# cbm2ram.net
KiCad netlist of a schematic drawn in EAGLE
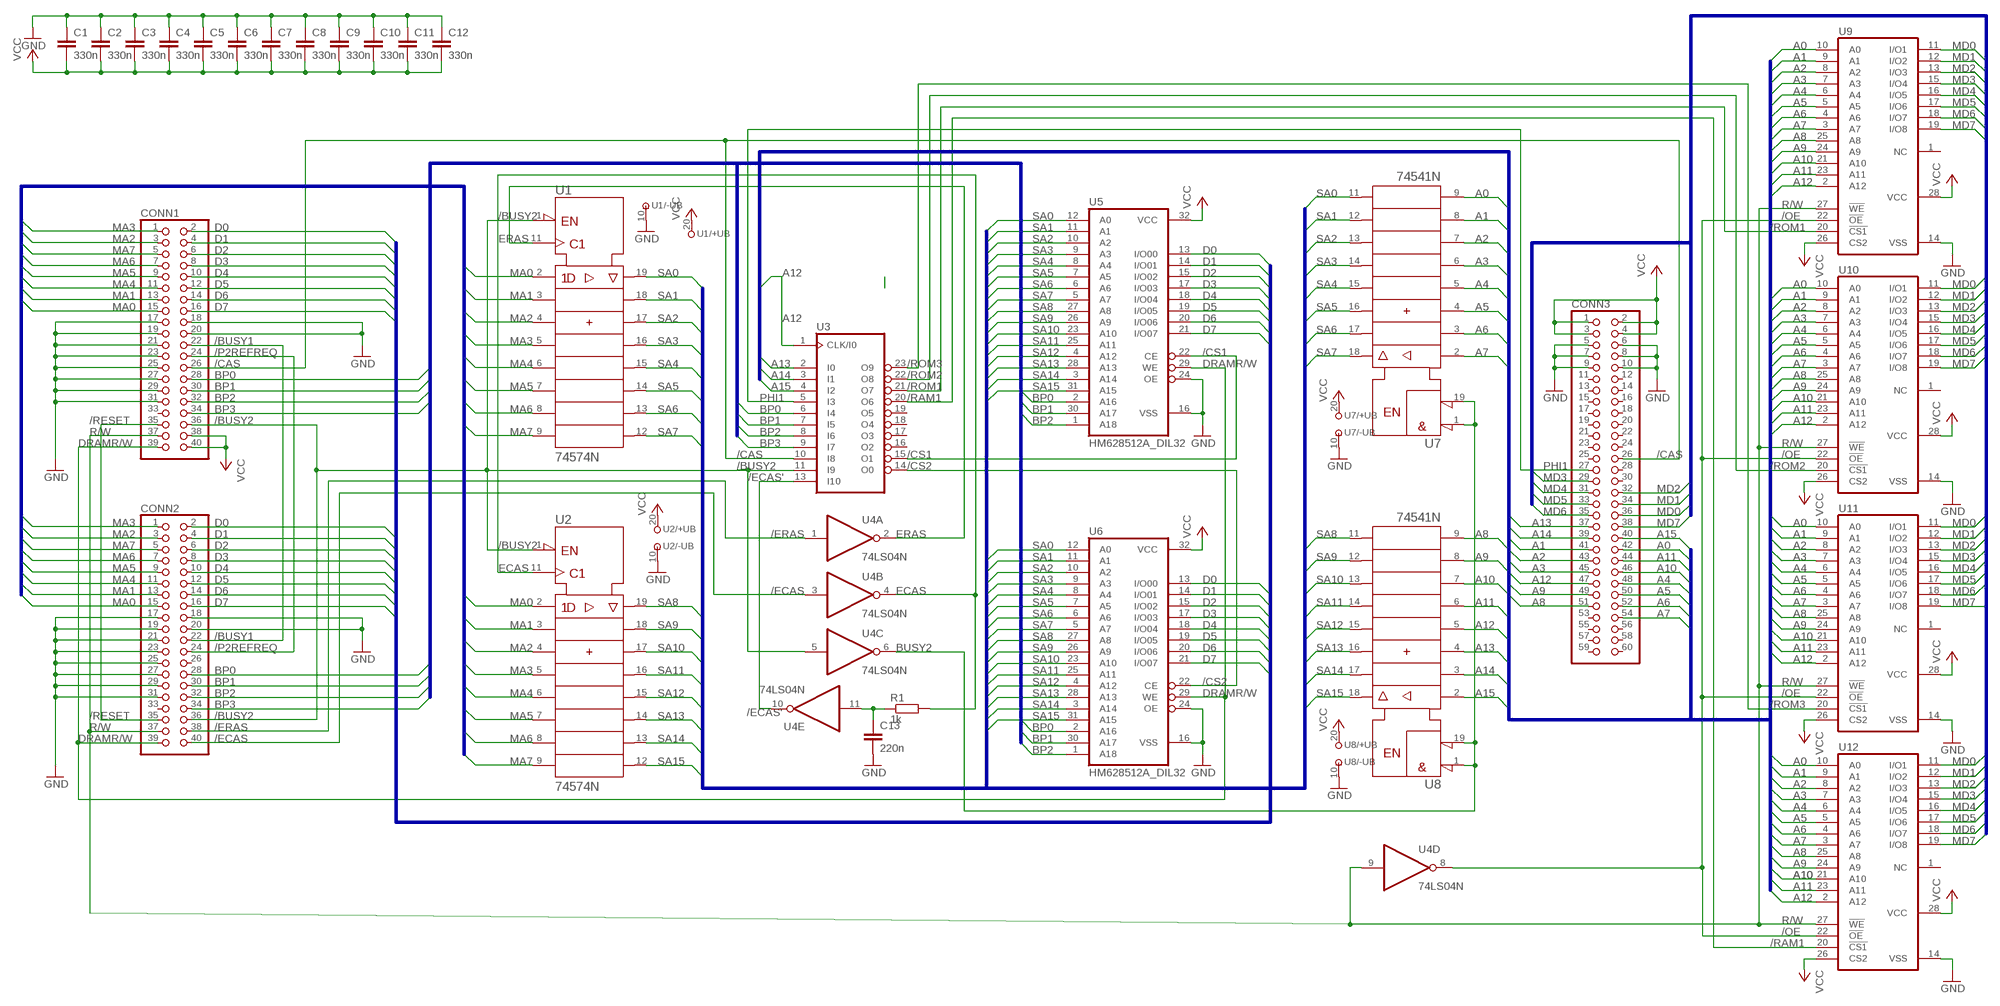
[diagram p0: schematic, sheet 1]

(export (version "E")
  (design (tool "Eeschema 10.0.6"))
  (components
    (comp (ref "C1")
      (value "330n")
      (footprint "eagle-import:C5B3")
      (libsource (lib "eagle-import") (part "C5/3"))
    )
    (comp (ref "C2")
      (value "330n")
      (footprint "eagle-import:C5B3")
      (libsource (lib "eagle-import") (part "C5/3"))
    )
    (comp (ref "C3")
      (value "330n")
      (footprint "eagle-import:C5B3")
      (libsource (lib "eagle-import") (part "C5/3"))
    )
    (comp (ref "C4")
      (value "330n")
      (footprint "eagle-import:C5B3")
      (libsource (lib "eagle-import") (part "C5/3"))
    )
    (comp (ref "C5")
      (value "330n")
      (footprint "eagle-import:C5B3")
      (libsource (lib "eagle-import") (part "C5/3"))
    )
    (comp (ref "C6")
      (value "330n")
      (footprint "eagle-import:C5B3")
      (libsource (lib "eagle-import") (part "C5/3"))
    )
    (comp (ref "C7")
      (value "330n")
      (footprint "eagle-import:C5B3")
      (libsource (lib "eagle-import") (part "C5/3"))
    )
    (comp (ref "C8")
      (value "330n")
      (footprint "eagle-import:C5B3")
      (libsource (lib "eagle-import") (part "C5/3"))
    )
    (comp (ref "C9")
      (value "330n")
      (footprint "eagle-import:C5B3")
      (libsource (lib "eagle-import") (part "C5/3"))
    )
    (comp (ref "C10")
      (value "330n")
      (footprint "eagle-import:C5B3")
      (libsource (lib "eagle-import") (part "C5/3"))
    )
    (comp (ref "C11")
      (value "330n")
      (footprint "eagle-import:C5B3")
      (libsource (lib "eagle-import") (part "C5/3"))
    )
    (comp (ref "C12")
      (value "330n")
      (footprint "eagle-import:C5B3")
      (libsource (lib "eagle-import") (part "C5/3"))
    )
    (comp (ref "C13")
      (value "220n")
      (footprint "eagle-import:C5B3")
      (libsource (lib "eagle-import") (part "C5/3"))
    )
    (comp (ref "CONN1")
      (value "PINHD-2X20")
      (footprint "eagle-import:2X20")
      (libsource (lib "eagle-import") (part "PINHD-2X20"))
    )
    (comp (ref "CONN2")
      (value "PINHD-2X20")
      (footprint "eagle-import:2X20")
      (libsource (lib "eagle-import") (part "PINHD-2X20"))
    )
    (comp (ref "CONN3")
      (value "PINHD-2X30")
      (footprint "eagle-import:2X30")
      (libsource (lib "eagle-import") (part "PINHD-2X30"))
    )
    (comp (ref "R1")
      (value "1k")
      (footprint "eagle-import:0207_10")
      (libsource (lib "eagle-import") (part "R-EU_0207/10"))
    )
    (comp (ref "U1")
      (value "74574N")
      (footprint "eagle-import:DIL20")
      (libsource (lib "eagle-import") (part "74574N"))
    )
    (comp (ref "U2")
      (value "74574N")
      (footprint "eagle-import:DIL20")
      (libsource (lib "eagle-import") (part "74574N"))
    )
    (comp (ref "U3")
      (value "22V10")
      (footprint "eagle-import:DIL24-3")
      (fields (field (name "MPN") "GAL22V10D-7LPN"))
      (libsource (lib "eagle-import") (part "22V10"))
    )
    (comp (ref "U4")
      (value "74LS04N")
      (footprint "eagle-import:DIL14")
      (libsource (lib "eagle-import") (part "7404NLS"))
    )
    (comp (ref "U5")
      (value "HM628512A_DIL32")
      (footprint "eagle-import:DIL32")
      (libsource (lib "eagle-import") (part "HM628512A_DIL32"))
    )
    (comp (ref "U6")
      (value "HM628512A_DIL32")
      (footprint "eagle-import:DIL32")
      (libsource (lib "eagle-import") (part "HM628512A_DIL32"))
    )
    (comp (ref "U7")
      (value "74541N")
      (footprint "eagle-import:DIL20")
      (libsource (lib "eagle-import") (part "74541N"))
    )
    (comp (ref "U8")
      (value "74541N")
      (footprint "eagle-import:DIL20")
      (libsource (lib "eagle-import") (part "74541N"))
    )
    (comp (ref "U9")
      (value "6264A")
      (footprint "eagle-import:DIL28-6")
      (libsource (lib "eagle-import") (part "6264A"))
    )
    (comp (ref "U10")
      (value "6264A")
      (footprint "eagle-import:DIL28-6")
      (libsource (lib "eagle-import") (part "6264A"))
    )
    (comp (ref "U11")
      (value "6264A")
      (footprint "eagle-import:DIL28-6")
      (libsource (lib "eagle-import") (part "6264A"))
    )
    (comp (ref "U12")
      (value "6264A")
      (footprint "eagle-import:DIL28-6")
      (libsource (lib "eagle-import") (part "6264A"))
    )
  )
  (nets
    (net (code "1") (name "/A0") (class "Default")
      (node (ref "CONN3") (pin "42") (pinfunction "42_42") (pintype "passive"))
      (node (ref "U10") (pin "10") (pinfunction "A0_10") (pintype "input"))
      (node (ref "U11") (pin "10") (pinfunction "A0_10") (pintype "input"))
      (node (ref "U12") (pin "10") (pinfunction "A0_10") (pintype "input"))
      (node (ref "U7") (pin "9") (pinfunction "A8_9") (pintype "input"))
      (node (ref "U9") (pin "10") (pinfunction "A0_10") (pintype "input"))
    )
    (net (code "2") (name "/A1") (class "Default")
      (node (ref "CONN3") (pin "41") (pinfunction "41_41") (pintype "passive"))
      (node (ref "U10") (pin "9") (pinfunction "A1_9") (pintype "input"))
      (node (ref "U11") (pin "9") (pinfunction "A1_9") (pintype "input"))
      (node (ref "U12") (pin "9") (pinfunction "A1_9") (pintype "input"))
      (node (ref "U7") (pin "8") (pinfunction "A7_8") (pintype "input"))
      (node (ref "U9") (pin "9") (pinfunction "A1_9") (pintype "input"))
    )
    (net (code "3") (name "/A2") (class "Default")
      (node (ref "CONN3") (pin "43") (pinfunction "43_43") (pintype "passive"))
      (node (ref "U10") (pin "8") (pinfunction "A2_8") (pintype "input"))
      (node (ref "U11") (pin "8") (pinfunction "A2_8") (pintype "input"))
      (node (ref "U12") (pin "8") (pinfunction "A2_8") (pintype "input"))
      (node (ref "U7") (pin "7") (pinfunction "A6_7") (pintype "input"))
      (node (ref "U9") (pin "8") (pinfunction "A2_8") (pintype "input"))
    )
    (net (code "4") (name "/A3") (class "Default")
      (node (ref "CONN3") (pin "45") (pinfunction "45_45") (pintype "passive"))
      (node (ref "U10") (pin "7") (pinfunction "A3_7") (pintype "input"))
      (node (ref "U11") (pin "7") (pinfunction "A3_7") (pintype "input"))
      (node (ref "U12") (pin "7") (pinfunction "A3_7") (pintype "input"))
      (node (ref "U7") (pin "6") (pinfunction "A5_6") (pintype "input"))
      (node (ref "U9") (pin "7") (pinfunction "A3_7") (pintype "input"))
    )
    (net (code "5") (name "/A4") (class "Default")
      (node (ref "CONN3") (pin "48") (pinfunction "48_48") (pintype "passive"))
      (node (ref "U10") (pin "6") (pinfunction "A4_6") (pintype "input"))
      (node (ref "U11") (pin "6") (pinfunction "A4_6") (pintype "input"))
      (node (ref "U12") (pin "6") (pinfunction "A4_6") (pintype "input"))
      (node (ref "U7") (pin "5") (pinfunction "A4_5") (pintype "input"))
      (node (ref "U9") (pin "6") (pinfunction "A4_6") (pintype "input"))
    )
    (net (code "6") (name "/A5") (class "Default")
      (node (ref "CONN3") (pin "50") (pinfunction "50_50") (pintype "passive"))
      (node (ref "U10") (pin "5") (pinfunction "A5_5") (pintype "input"))
      (node (ref "U11") (pin "5") (pinfunction "A5_5") (pintype "input"))
      (node (ref "U12") (pin "5") (pinfunction "A5_5") (pintype "input"))
      (node (ref "U7") (pin "4") (pinfunction "A3_4") (pintype "input"))
      (node (ref "U9") (pin "5") (pinfunction "A5_5") (pintype "input"))
    )
    (net (code "7") (name "/A6") (class "Default")
      (node (ref "CONN3") (pin "52") (pinfunction "52_52") (pintype "passive"))
      (node (ref "U10") (pin "4") (pinfunction "A6_4") (pintype "input"))
      (node (ref "U11") (pin "4") (pinfunction "A6_4") (pintype "input"))
      (node (ref "U12") (pin "4") (pinfunction "A6_4") (pintype "input"))
      (node (ref "U7") (pin "3") (pinfunction "A2_3") (pintype "input"))
      (node (ref "U9") (pin "4") (pinfunction "A6_4") (pintype "input"))
    )
    (net (code "8") (name "/A7") (class "Default")
      (node (ref "CONN3") (pin "54") (pinfunction "54_54") (pintype "passive"))
      (node (ref "U10") (pin "3") (pinfunction "A7_3") (pintype "input"))
      (node (ref "U11") (pin "3") (pinfunction "A7_3") (pintype "input"))
      (node (ref "U12") (pin "3") (pinfunction "A7_3") (pintype "input"))
      (node (ref "U7") (pin "2") (pinfunction "A1_2") (pintype "input"))
      (node (ref "U9") (pin "3") (pinfunction "A7_3") (pintype "input"))
    )
    (net (code "9") (name "/A8") (class "Default")
      (node (ref "CONN3") (pin "51") (pinfunction "51_51") (pintype "passive"))
      (node (ref "U10") (pin "25") (pinfunction "A8_25") (pintype "input"))
      (node (ref "U11") (pin "25") (pinfunction "A8_25") (pintype "input"))
      (node (ref "U12") (pin "25") (pinfunction "A8_25") (pintype "input"))
      (node (ref "U8") (pin "9") (pinfunction "A8_9") (pintype "input"))
      (node (ref "U9") (pin "25") (pinfunction "A8_25") (pintype "input"))
    )
    (net (code "10") (name "/A9") (class "Default")
      (node (ref "CONN3") (pin "49") (pinfunction "49_49") (pintype "passive"))
      (node (ref "U10") (pin "24") (pinfunction "A9_24") (pintype "input"))
      (node (ref "U11") (pin "24") (pinfunction "A9_24") (pintype "input"))
      (node (ref "U12") (pin "24") (pinfunction "A9_24") (pintype "input"))
      (node (ref "U8") (pin "8") (pinfunction "A7_8") (pintype "input"))
      (node (ref "U9") (pin "24") (pinfunction "A9_24") (pintype "input"))
    )
    (net (code "11") (name "/A10") (class "Default")
      (node (ref "CONN3") (pin "46") (pinfunction "46_46") (pintype "passive"))
      (node (ref "U10") (pin "21") (pinfunction "A10_21") (pintype "input"))
      (node (ref "U11") (pin "21") (pinfunction "A10_21") (pintype "input"))
      (node (ref "U12") (pin "21") (pinfunction "A10_21") (pintype "input"))
      (node (ref "U8") (pin "7") (pinfunction "A6_7") (pintype "input"))
      (node (ref "U9") (pin "21") (pinfunction "A10_21") (pintype "input"))
    )
    (net (code "12") (name "/A11") (class "Default")
      (node (ref "CONN3") (pin "44") (pinfunction "44_44") (pintype "passive"))
      (node (ref "U10") (pin "23") (pinfunction "A11_23") (pintype "input"))
      (node (ref "U11") (pin "23") (pinfunction "A11_23") (pintype "input"))
      (node (ref "U12") (pin "23") (pinfunction "A11_23") (pintype "input"))
      (node (ref "U8") (pin "6") (pinfunction "A5_6") (pintype "input"))
      (node (ref "U9") (pin "23") (pinfunction "A11_23") (pintype "input"))
    )
    (net (code "13") (name "/A12") (class "Default")
      (node (ref "CONN3") (pin "47") (pinfunction "47_47") (pintype "passive"))
      (node (ref "U10") (pin "2") (pinfunction "A12_2") (pintype "input"))
      (node (ref "U11") (pin "2") (pinfunction "A12_2") (pintype "input"))
      (node (ref "U12") (pin "2") (pinfunction "A12_2") (pintype "input"))
      (node (ref "U3") (pin "1") (pinfunction "CLK/I0_1") (pintype "input"))
      (node (ref "U8") (pin "5") (pinfunction "A4_5") (pintype "input"))
      (node (ref "U9") (pin "2") (pinfunction "A12_2") (pintype "input"))
    )
    (net (code "14") (name "/A13") (class "Default")
      (node (ref "CONN3") (pin "37") (pinfunction "37_37") (pintype "passive"))
      (node (ref "U3") (pin "2") (pinfunction "I0_2") (pintype "input"))
      (node (ref "U8") (pin "4") (pinfunction "A3_4") (pintype "input"))
    )
    (net (code "15") (name "/A14") (class "Default")
      (node (ref "CONN3") (pin "39") (pinfunction "39_39") (pintype "passive"))
      (node (ref "U3") (pin "3") (pinfunction "I1_3") (pintype "input"))
      (node (ref "U8") (pin "3") (pinfunction "A2_3") (pintype "input"))
    )
    (net (code "16") (name "/A15") (class "Default")
      (node (ref "CONN3") (pin "40") (pinfunction "40_40") (pintype "passive"))
      (node (ref "U3") (pin "4") (pinfunction "I2_4") (pintype "input"))
      (node (ref "U8") (pin "2") (pinfunction "A1_2") (pintype "input"))
    )
    (net (code "17") (name "/BP0") (class "Default")
      (node (ref "CONN1") (pin "28") (pinfunction "28_28") (pintype "passive"))
      (node (ref "CONN2") (pin "28") (pinfunction "28_28") (pintype "passive"))
      (node (ref "U3") (pin "6") (pinfunction "I4_6") (pintype "input"))
      (node (ref "U5") (pin "2") (pinfunction "A16_2") (pintype "input"))
      (node (ref "U6") (pin "2") (pinfunction "A16_2") (pintype "input"))
    )
    (net (code "18") (name "/BP1") (class "Default")
      (node (ref "CONN1") (pin "30") (pinfunction "30_30") (pintype "passive"))
      (node (ref "CONN2") (pin "30") (pinfunction "30_30") (pintype "passive"))
      (node (ref "U3") (pin "7") (pinfunction "I5_7") (pintype "input"))
      (node (ref "U5") (pin "30") (pinfunction "A17_30") (pintype "input"))
      (node (ref "U6") (pin "30") (pinfunction "A17_30") (pintype "input"))
    )
    (net (code "19") (name "/BP2") (class "Default")
      (node (ref "CONN1") (pin "32") (pinfunction "32_32") (pintype "passive"))
      (node (ref "CONN2") (pin "32") (pinfunction "32_32") (pintype "passive"))
      (node (ref "U3") (pin "8") (pinfunction "I6_8") (pintype "input"))
      (node (ref "U5") (pin "1") (pinfunction "A18_1") (pintype "input"))
      (node (ref "U6") (pin "1") (pinfunction "A18_1") (pintype "input"))
    )
    (net (code "20") (name "/BP3") (class "Default")
      (node (ref "CONN1") (pin "34") (pinfunction "34_34") (pintype "passive"))
      (node (ref "CONN2") (pin "34") (pinfunction "34_34") (pintype "passive"))
      (node (ref "U3") (pin "9") (pinfunction "I7_9") (pintype "input"))
    )
    (net (code "21") (name "/BUSY2") (class "Default")
      (node (ref "U4") (pin "6") (pinfunction "O_6") (pintype "output"))
      (node (ref "U7") (pin "1") (pinfunction "~{G1}_1") (pintype "input"))
      (node (ref "U7") (pin "19") (pinfunction "~{G2}_19") (pintype "input"))
      (node (ref "U8") (pin "1") (pinfunction "~{G1}_1") (pintype "input"))
      (node (ref "U8") (pin "19") (pinfunction "~{G2}_19") (pintype "input"))
    )
    (net (code "22") (name "/D0") (class "Default")
      (node (ref "CONN1") (pin "2") (pinfunction "2_2") (pintype "passive"))
      (node (ref "CONN2") (pin "2") (pinfunction "2_2") (pintype "passive"))
      (node (ref "U5") (pin "13") (pinfunction "I/O00_13") (pintype "bidirectional"))
      (node (ref "U6") (pin "13") (pinfunction "I/O00_13") (pintype "bidirectional"))
    )
    (net (code "23") (name "/D1") (class "Default")
      (node (ref "CONN1") (pin "4") (pinfunction "4_4") (pintype "passive"))
      (node (ref "CONN2") (pin "4") (pinfunction "4_4") (pintype "passive"))
      (node (ref "U5") (pin "14") (pinfunction "I/O01_14") (pintype "bidirectional"))
      (node (ref "U6") (pin "14") (pinfunction "I/O01_14") (pintype "bidirectional"))
    )
    (net (code "24") (name "/D2") (class "Default")
      (node (ref "CONN1") (pin "6") (pinfunction "6_6") (pintype "passive"))
      (node (ref "CONN2") (pin "6") (pinfunction "6_6") (pintype "passive"))
      (node (ref "U5") (pin "15") (pinfunction "I/O02_15") (pintype "bidirectional"))
      (node (ref "U6") (pin "15") (pinfunction "I/O02_15") (pintype "bidirectional"))
    )
    (net (code "25") (name "/D3") (class "Default")
      (node (ref "CONN1") (pin "8") (pinfunction "8_8") (pintype "passive"))
      (node (ref "CONN2") (pin "8") (pinfunction "8_8") (pintype "passive"))
      (node (ref "U5") (pin "17") (pinfunction "I/O03_17") (pintype "bidirectional"))
      (node (ref "U6") (pin "17") (pinfunction "I/O03_17") (pintype "bidirectional"))
    )
    (net (code "26") (name "/D4") (class "Default")
      (node (ref "CONN1") (pin "10") (pinfunction "10_10") (pintype "passive"))
      (node (ref "CONN2") (pin "10") (pinfunction "10_10") (pintype "passive"))
      (node (ref "U5") (pin "18") (pinfunction "I/O04_18") (pintype "bidirectional"))
      (node (ref "U6") (pin "18") (pinfunction "I/O04_18") (pintype "bidirectional"))
    )
    (net (code "27") (name "/D5") (class "Default")
      (node (ref "CONN1") (pin "12") (pinfunction "12_12") (pintype "passive"))
      (node (ref "CONN2") (pin "12") (pinfunction "12_12") (pintype "passive"))
      (node (ref "U5") (pin "19") (pinfunction "I/O05_19") (pintype "bidirectional"))
      (node (ref "U6") (pin "19") (pinfunction "I/O05_19") (pintype "bidirectional"))
    )
    (net (code "28") (name "/D6") (class "Default")
      (node (ref "CONN1") (pin "14") (pinfunction "14_14") (pintype "passive"))
      (node (ref "CONN2") (pin "14") (pinfunction "14_14") (pintype "passive"))
      (node (ref "U5") (pin "20") (pinfunction "I/O06_20") (pintype "bidirectional"))
      (node (ref "U6") (pin "20") (pinfunction "I/O06_20") (pintype "bidirectional"))
    )
    (net (code "29") (name "/D7") (class "Default")
      (node (ref "CONN1") (pin "16") (pinfunction "16_16") (pintype "passive"))
      (node (ref "CONN2") (pin "16") (pinfunction "16_16") (pintype "passive"))
      (node (ref "U5") (pin "21") (pinfunction "I/O07_21") (pintype "bidirectional"))
      (node (ref "U6") (pin "21") (pinfunction "I/O07_21") (pintype "bidirectional"))
    )
    (net (code "30") (name "/DRAMR{slash}W") (class "Default")
      (node (ref "CONN1") (pin "39") (pinfunction "39_39") (pintype "passive"))
      (node (ref "CONN2") (pin "39") (pinfunction "39_39") (pintype "passive"))
      (node (ref "U5") (pin "29") (pinfunction "WE_29") (pintype "input"))
      (node (ref "U6") (pin "29") (pinfunction "WE_29") (pintype "input"))
    )
    (net (code "31") (name "/ECAS") (class "Default")
      (node (ref "R1") (pin "2") (pinfunction "2_2") (pintype "passive"))
      (node (ref "U2") (pin "11") (pinfunction "CLK_11") (pintype "input"))
      (node (ref "U4") (pin "4") (pinfunction "O_4") (pintype "output"))
    )
    (net (code "32") (name "/ERAS") (class "Default")
      (node (ref "U1") (pin "11") (pinfunction "CLK_11") (pintype "input"))
      (node (ref "U4") (pin "2") (pinfunction "O_2") (pintype "output"))
    )
    (net (code "33") (name "/MA0") (class "Default")
      (node (ref "CONN1") (pin "15") (pinfunction "15_15") (pintype "passive"))
      (node (ref "CONN2") (pin "15") (pinfunction "15_15") (pintype "passive"))
      (node (ref "U1") (pin "2") (pinfunction "1D_2") (pintype "input"))
      (node (ref "U2") (pin "2") (pinfunction "1D_2") (pintype "input"))
    )
    (net (code "34") (name "/MA1") (class "Default")
      (node (ref "CONN1") (pin "13") (pinfunction "13_13") (pintype "passive"))
      (node (ref "CONN2") (pin "13") (pinfunction "13_13") (pintype "passive"))
      (node (ref "U1") (pin "3") (pinfunction "2D_3") (pintype "input"))
      (node (ref "U2") (pin "3") (pinfunction "2D_3") (pintype "input"))
    )
    (net (code "35") (name "/MA2") (class "Default")
      (node (ref "CONN1") (pin "3") (pinfunction "3_3") (pintype "passive"))
      (node (ref "CONN2") (pin "3") (pinfunction "3_3") (pintype "passive"))
      (node (ref "U1") (pin "4") (pinfunction "3D_4") (pintype "input"))
      (node (ref "U2") (pin "4") (pinfunction "3D_4") (pintype "input"))
    )
    (net (code "36") (name "/MA3") (class "Default")
      (node (ref "CONN1") (pin "1") (pinfunction "1_1") (pintype "passive"))
      (node (ref "CONN2") (pin "1") (pinfunction "1_1") (pintype "passive"))
      (node (ref "U1") (pin "5") (pinfunction "4D_5") (pintype "input"))
      (node (ref "U2") (pin "5") (pinfunction "4D_5") (pintype "input"))
    )
    (net (code "37") (name "/MA4") (class "Default")
      (node (ref "CONN1") (pin "11") (pinfunction "11_11") (pintype "passive"))
      (node (ref "CONN2") (pin "11") (pinfunction "11_11") (pintype "passive"))
      (node (ref "U1") (pin "6") (pinfunction "5D_6") (pintype "input"))
      (node (ref "U2") (pin "6") (pinfunction "5D_6") (pintype "input"))
    )
    (net (code "38") (name "/MA5") (class "Default")
      (node (ref "CONN1") (pin "9") (pinfunction "9_9") (pintype "passive"))
      (node (ref "CONN2") (pin "9") (pinfunction "9_9") (pintype "passive"))
      (node (ref "U1") (pin "7") (pinfunction "6D_7") (pintype "input"))
      (node (ref "U2") (pin "7") (pinfunction "6D_7") (pintype "input"))
    )
    (net (code "39") (name "/MA6") (class "Default")
      (node (ref "CONN1") (pin "7") (pinfunction "7_7") (pintype "passive"))
      (node (ref "CONN2") (pin "7") (pinfunction "7_7") (pintype "passive"))
      (node (ref "U1") (pin "8") (pinfunction "7D_8") (pintype "input"))
      (node (ref "U2") (pin "8") (pinfunction "7D_8") (pintype "input"))
    )
    (net (code "40") (name "/MA7") (class "Default")
      (node (ref "CONN1") (pin "5") (pinfunction "5_5") (pintype "passive"))
      (node (ref "CONN2") (pin "5") (pinfunction "5_5") (pintype "passive"))
      (node (ref "U1") (pin "9") (pinfunction "8D_9") (pintype "input"))
      (node (ref "U2") (pin "9") (pinfunction "8D_9") (pintype "input"))
    )
    (net (code "41") (name "/MD0") (class "Default")
      (node (ref "CONN3") (pin "36") (pinfunction "36_36") (pintype "passive"))
      (node (ref "U10") (pin "11") (pinfunction "I/O1_11") (pintype "bidirectional"))
      (node (ref "U11") (pin "11") (pinfunction "I/O1_11") (pintype "bidirectional"))
      (node (ref "U12") (pin "11") (pinfunction "I/O1_11") (pintype "bidirectional"))
      (node (ref "U9") (pin "11") (pinfunction "I/O1_11") (pintype "bidirectional"))
    )
    (net (code "42") (name "/MD1") (class "Default")
      (node (ref "CONN3") (pin "34") (pinfunction "34_34") (pintype "passive"))
      (node (ref "U10") (pin "12") (pinfunction "I/O2_12") (pintype "bidirectional"))
      (node (ref "U11") (pin "12") (pinfunction "I/O2_12") (pintype "bidirectional"))
      (node (ref "U12") (pin "12") (pinfunction "I/O2_12") (pintype "bidirectional"))
      (node (ref "U9") (pin "12") (pinfunction "I/O2_12") (pintype "bidirectional"))
    )
    (net (code "43") (name "/MD2") (class "Default")
      (node (ref "CONN3") (pin "32") (pinfunction "32_32") (pintype "passive"))
      (node (ref "U10") (pin "13") (pinfunction "I/O3_13") (pintype "bidirectional"))
      (node (ref "U11") (pin "13") (pinfunction "I/O3_13") (pintype "bidirectional"))
      (node (ref "U12") (pin "13") (pinfunction "I/O3_13") (pintype "bidirectional"))
      (node (ref "U9") (pin "13") (pinfunction "I/O3_13") (pintype "bidirectional"))
    )
    (net (code "44") (name "/MD3") (class "Default")
      (node (ref "CONN3") (pin "29") (pinfunction "29_29") (pintype "passive"))
      (node (ref "U10") (pin "15") (pinfunction "I/O4_15") (pintype "bidirectional"))
      (node (ref "U11") (pin "15") (pinfunction "I/O4_15") (pintype "bidirectional"))
      (node (ref "U12") (pin "15") (pinfunction "I/O4_15") (pintype "bidirectional"))
      (node (ref "U9") (pin "15") (pinfunction "I/O4_15") (pintype "bidirectional"))
    )
    (net (code "45") (name "/MD4") (class "Default")
      (node (ref "CONN3") (pin "31") (pinfunction "31_31") (pintype "passive"))
      (node (ref "U10") (pin "16") (pinfunction "I/O5_16") (pintype "bidirectional"))
      (node (ref "U11") (pin "16") (pinfunction "I/O5_16") (pintype "bidirectional"))
      (node (ref "U12") (pin "16") (pinfunction "I/O5_16") (pintype "bidirectional"))
      (node (ref "U9") (pin "16") (pinfunction "I/O5_16") (pintype "bidirectional"))
    )
    (net (code "46") (name "/MD5") (class "Default")
      (node (ref "CONN3") (pin "33") (pinfunction "33_33") (pintype "passive"))
      (node (ref "U10") (pin "17") (pinfunction "I/O6_17") (pintype "bidirectional"))
      (node (ref "U11") (pin "17") (pinfunction "I/O6_17") (pintype "bidirectional"))
      (node (ref "U12") (pin "17") (pinfunction "I/O6_17") (pintype "bidirectional"))
      (node (ref "U9") (pin "17") (pinfunction "I/O6_17") (pintype "bidirectional"))
    )
    (net (code "47") (name "/MD6") (class "Default")
      (node (ref "CONN3") (pin "35") (pinfunction "35_35") (pintype "passive"))
      (node (ref "U10") (pin "18") (pinfunction "I/O7_18") (pintype "bidirectional"))
      (node (ref "U11") (pin "18") (pinfunction "I/O7_18") (pintype "bidirectional"))
      (node (ref "U12") (pin "18") (pinfunction "I/O7_18") (pintype "bidirectional"))
      (node (ref "U9") (pin "18") (pinfunction "I/O7_18") (pintype "bidirectional"))
    )
    (net (code "48") (name "/MD7") (class "Default")
      (node (ref "CONN3") (pin "38") (pinfunction "38_38") (pintype "passive"))
      (node (ref "U10") (pin "19") (pinfunction "I/O8_19") (pintype "bidirectional"))
      (node (ref "U11") (pin "19") (pinfunction "I/O8_19") (pintype "bidirectional"))
      (node (ref "U12") (pin "19") (pinfunction "I/O8_19") (pintype "bidirectional"))
      (node (ref "U9") (pin "19") (pinfunction "I/O8_19") (pintype "bidirectional"))
    )
    (net (code "49") (name "/PHI1") (class "Default")
      (node (ref "CONN3") (pin "27") (pinfunction "27_27") (pintype "passive"))
      (node (ref "U3") (pin "5") (pinfunction "I3_5") (pintype "input"))
    )
    (net (code "50") (name "/R{slash}W") (class "Default")
      (node (ref "CONN1") (pin "37") (pinfunction "37_37") (pintype "passive"))
      (node (ref "CONN2") (pin "37") (pinfunction "37_37") (pintype "passive"))
      (node (ref "U10") (pin "27") (pinfunction "~{WE}_27") (pintype "input"))
      (node (ref "U11") (pin "27") (pinfunction "~{WE}_27") (pintype "input"))
      (node (ref "U12") (pin "27") (pinfunction "~{WE}_27") (pintype "input"))
      (node (ref "U4") (pin "9") (pinfunction "I_9") (pintype "input"))
      (node (ref "U9") (pin "27") (pinfunction "~{WE}_27") (pintype "input"))
    )
    (net (code "51") (name "/SA0") (class "Default")
      (node (ref "U1") (pin "19") (pinfunction "1Q_19") (pintype "tri_state"))
      (node (ref "U5") (pin "12") (pinfunction "A0_12") (pintype "input"))
      (node (ref "U6") (pin "12") (pinfunction "A0_12") (pintype "input"))
      (node (ref "U7") (pin "11") (pinfunction "Y8_11") (pintype "tri_state"))
    )
    (net (code "52") (name "/SA1") (class "Default")
      (node (ref "U1") (pin "18") (pinfunction "2Q_18") (pintype "tri_state"))
      (node (ref "U5") (pin "11") (pinfunction "A1_11") (pintype "input"))
      (node (ref "U6") (pin "11") (pinfunction "A1_11") (pintype "input"))
      (node (ref "U7") (pin "12") (pinfunction "Y7_12") (pintype "tri_state"))
    )
    (net (code "53") (name "/SA2") (class "Default")
      (node (ref "U1") (pin "17") (pinfunction "3Q_17") (pintype "tri_state"))
      (node (ref "U5") (pin "10") (pinfunction "A2_10") (pintype "input"))
      (node (ref "U6") (pin "10") (pinfunction "A2_10") (pintype "input"))
      (node (ref "U7") (pin "13") (pinfunction "Y6_13") (pintype "tri_state"))
    )
    (net (code "54") (name "/SA3") (class "Default")
      (node (ref "U1") (pin "16") (pinfunction "4Q_16") (pintype "tri_state"))
      (node (ref "U5") (pin "9") (pinfunction "A3_9") (pintype "input"))
      (node (ref "U6") (pin "9") (pinfunction "A3_9") (pintype "input"))
      (node (ref "U7") (pin "14") (pinfunction "Y5_14") (pintype "tri_state"))
    )
    (net (code "55") (name "/SA4") (class "Default")
      (node (ref "U1") (pin "15") (pinfunction "5Q_15") (pintype "tri_state"))
      (node (ref "U5") (pin "8") (pinfunction "A4_8") (pintype "input"))
      (node (ref "U6") (pin "8") (pinfunction "A4_8") (pintype "input"))
      (node (ref "U7") (pin "15") (pinfunction "Y4_15") (pintype "tri_state"))
    )
    (net (code "56") (name "/SA5") (class "Default")
      (node (ref "U1") (pin "14") (pinfunction "6Q_14") (pintype "tri_state"))
      (node (ref "U5") (pin "7") (pinfunction "A5_7") (pintype "input"))
      (node (ref "U6") (pin "7") (pinfunction "A5_7") (pintype "input"))
      (node (ref "U7") (pin "16") (pinfunction "Y3_16") (pintype "tri_state"))
    )
    (net (code "57") (name "/SA6") (class "Default")
      (node (ref "U1") (pin "13") (pinfunction "7Q_13") (pintype "tri_state"))
      (node (ref "U5") (pin "6") (pinfunction "A6_6") (pintype "input"))
      (node (ref "U6") (pin "6") (pinfunction "A6_6") (pintype "input"))
      (node (ref "U7") (pin "17") (pinfunction "Y2_17") (pintype "tri_state"))
    )
    (net (code "58") (name "/SA7") (class "Default")
      (node (ref "U1") (pin "12") (pinfunction "8Q_12") (pintype "tri_state"))
      (node (ref "U5") (pin "5") (pinfunction "A7_5") (pintype "input"))
      (node (ref "U6") (pin "5") (pinfunction "A7_5") (pintype "input"))
      (node (ref "U7") (pin "18") (pinfunction "Y1_18") (pintype "tri_state"))
    )
    (net (code "59") (name "/SA8") (class "Default")
      (node (ref "U2") (pin "19") (pinfunction "1Q_19") (pintype "tri_state"))
      (node (ref "U5") (pin "27") (pinfunction "A8_27") (pintype "input"))
      (node (ref "U6") (pin "27") (pinfunction "A8_27") (pintype "input"))
      (node (ref "U8") (pin "11") (pinfunction "Y8_11") (pintype "tri_state"))
    )
    (net (code "60") (name "/SA9") (class "Default")
      (node (ref "U2") (pin "18") (pinfunction "2Q_18") (pintype "tri_state"))
      (node (ref "U5") (pin "26") (pinfunction "A9_26") (pintype "input"))
      (node (ref "U6") (pin "26") (pinfunction "A9_26") (pintype "input"))
      (node (ref "U8") (pin "12") (pinfunction "Y7_12") (pintype "tri_state"))
    )
    (net (code "61") (name "/SA10") (class "Default")
      (node (ref "U2") (pin "17") (pinfunction "3Q_17") (pintype "tri_state"))
      (node (ref "U5") (pin "23") (pinfunction "A10_23") (pintype "input"))
      (node (ref "U6") (pin "23") (pinfunction "A10_23") (pintype "input"))
      (node (ref "U8") (pin "13") (pinfunction "Y6_13") (pintype "tri_state"))
    )
    (net (code "62") (name "/SA11") (class "Default")
      (node (ref "U2") (pin "16") (pinfunction "4Q_16") (pintype "tri_state"))
      (node (ref "U5") (pin "25") (pinfunction "A11_25") (pintype "input"))
      (node (ref "U6") (pin "25") (pinfunction "A11_25") (pintype "input"))
      (node (ref "U8") (pin "14") (pinfunction "Y5_14") (pintype "tri_state"))
    )
    (net (code "63") (name "/SA12") (class "Default")
      (node (ref "U2") (pin "15") (pinfunction "5Q_15") (pintype "tri_state"))
      (node (ref "U5") (pin "4") (pinfunction "A12_4") (pintype "input"))
      (node (ref "U6") (pin "4") (pinfunction "A12_4") (pintype "input"))
      (node (ref "U8") (pin "15") (pinfunction "Y4_15") (pintype "tri_state"))
    )
    (net (code "64") (name "/SA13") (class "Default")
      (node (ref "U2") (pin "14") (pinfunction "6Q_14") (pintype "tri_state"))
      (node (ref "U5") (pin "28") (pinfunction "A13_28") (pintype "input"))
      (node (ref "U6") (pin "28") (pinfunction "A13_28") (pintype "input"))
      (node (ref "U8") (pin "16") (pinfunction "Y3_16") (pintype "tri_state"))
    )
    (net (code "65") (name "/SA14") (class "Default")
      (node (ref "U2") (pin "13") (pinfunction "7Q_13") (pintype "tri_state"))
      (node (ref "U5") (pin "3") (pinfunction "A14_3") (pintype "input"))
      (node (ref "U6") (pin "3") (pinfunction "A14_3") (pintype "input"))
      (node (ref "U8") (pin "17") (pinfunction "Y2_17") (pintype "tri_state"))
    )
    (net (code "66") (name "/SA15") (class "Default")
      (node (ref "U2") (pin "12") (pinfunction "8Q_12") (pintype "tri_state"))
      (node (ref "U5") (pin "31") (pinfunction "A15_31") (pintype "input"))
      (node (ref "U6") (pin "31") (pinfunction "A15_31") (pintype "input"))
      (node (ref "U8") (pin "18") (pinfunction "Y1_18") (pintype "tri_state"))
    )
    (net (code "67") (name "/{slash}BUSY1") (class "Default")
      (node (ref "CONN1") (pin "22") (pinfunction "22_22") (pintype "passive"))
      (node (ref "CONN2") (pin "22") (pinfunction "22_22") (pintype "passive"))
    )
    (net (code "68") (name "/{slash}BUSY2") (class "Default")
      (node (ref "CONN1") (pin "36") (pinfunction "36_36") (pintype "passive"))
      (node (ref "CONN2") (pin "36") (pinfunction "36_36") (pintype "passive"))
      (node (ref "U1") (pin "1") (pinfunction "~{OC}_1") (pintype "input"))
      (node (ref "U2") (pin "1") (pinfunction "~{OC}_1") (pintype "input"))
      (node (ref "U3") (pin "11") (pinfunction "I9_11") (pintype "input"))
      (node (ref "U4") (pin "5") (pinfunction "I_5") (pintype "input"))
    )
    (net (code "69") (name "/{slash}CAS") (class "Default")
      (node (ref "CONN1") (pin "26") (pinfunction "26_26") (pintype "passive"))
      (node (ref "CONN3") (pin "26") (pinfunction "26_26") (pintype "passive"))
      (node (ref "U3") (pin "10") (pinfunction "I8_10") (pintype "input"))
    )
    (net (code "70") (name "/{slash}CS1") (class "Default")
      (node (ref "U3") (pin "15") (pinfunction "O1_15") (pintype "bidirectional"))
      (node (ref "U5") (pin "22") (pinfunction "CE_22") (pintype "input"))
    )
    (net (code "71") (name "/{slash}CS2") (class "Default")
      (node (ref "U3") (pin "14") (pinfunction "O0_14") (pintype "bidirectional"))
      (node (ref "U6") (pin "22") (pinfunction "CE_22") (pintype "input"))
    )
    (net (code "72") (name "/{slash}ECAS") (class "Default")
      (node (ref "CONN2") (pin "40") (pinfunction "40_40") (pintype "passive"))
      (node (ref "U4") (pin "3") (pinfunction "I_3") (pintype "input"))
    )
    (net (code "73") (name "/{slash}ECAS'") (class "Default")
      (node (ref "U3") (pin "13") (pinfunction "I10_13") (pintype "input"))
      (node (ref "U4") (pin "10") (pinfunction "O_10") (pintype "output"))
    )
    (net (code "74") (name "/{slash}ERAS") (class "Default")
      (node (ref "CONN2") (pin "38") (pinfunction "38_38") (pintype "passive"))
      (node (ref "U4") (pin "1") (pinfunction "I_1") (pintype "input"))
    )
    (net (code "75") (name "/{slash}OE") (class "Default")
      (node (ref "U10") (pin "22") (pinfunction "~{OE}_22") (pintype "input"))
      (node (ref "U11") (pin "22") (pinfunction "~{OE}_22") (pintype "input"))
      (node (ref "U12") (pin "22") (pinfunction "~{OE}_22") (pintype "input"))
      (node (ref "U4") (pin "8") (pinfunction "O_8") (pintype "output"))
      (node (ref "U9") (pin "22") (pinfunction "~{OE}_22") (pintype "input"))
    )
    (net (code "76") (name "/{slash}P2REFREQ") (class "Default")
      (node (ref "CONN1") (pin "24") (pinfunction "24_24") (pintype "passive"))
      (node (ref "CONN2") (pin "24") (pinfunction "24_24") (pintype "passive"))
    )
    (net (code "77") (name "/{slash}RAM1") (class "Default")
      (node (ref "U12") (pin "20") (pinfunction "~{CS1}_20") (pintype "input"))
      (node (ref "U3") (pin "20") (pinfunction "O6_20") (pintype "bidirectional"))
    )
    (net (code "78") (name "/{slash}RESET") (class "Default")
      (node (ref "CONN1") (pin "35") (pinfunction "35_35") (pintype "passive"))
      (node (ref "CONN2") (pin "35") (pinfunction "35_35") (pintype "passive"))
    )
    (net (code "79") (name "/{slash}ROM1") (class "Default")
      (node (ref "U3") (pin "21") (pinfunction "O7_21") (pintype "bidirectional"))
      (node (ref "U9") (pin "20") (pinfunction "~{CS1}_20") (pintype "input"))
    )
    (net (code "80") (name "/{slash}ROM2") (class "Default")
      (node (ref "U10") (pin "20") (pinfunction "~{CS1}_20") (pintype "input"))
      (node (ref "U3") (pin "22") (pinfunction "O8_22") (pintype "bidirectional"))
    )
    (net (code "81") (name "/{slash}ROM3") (class "Default")
      (node (ref "U11") (pin "20") (pinfunction "~{CS1}_20") (pintype "input"))
      (node (ref "U3") (pin "23") (pinfunction "O9_23") (pintype "bidirectional"))
    )
    (net (code "82") (name "GND") (class "Default")
      (node (ref "C1") (pin "1") (pinfunction "1_1") (pintype "passive"))
      (node (ref "C10") (pin "1") (pinfunction "1_1") (pintype "passive"))
      (node (ref "C11") (pin "1") (pinfunction "1_1") (pintype "passive"))
      (node (ref "C12") (pin "1") (pinfunction "1_1") (pintype "passive"))
      (node (ref "C13") (pin "2") (pinfunction "2_2") (pintype "passive"))
      (node (ref "C2") (pin "1") (pinfunction "1_1") (pintype "passive"))
      (node (ref "C3") (pin "1") (pinfunction "1_1") (pintype "passive"))
      (node (ref "C4") (pin "1") (pinfunction "1_1") (pintype "passive"))
      (node (ref "C5") (pin "1") (pinfunction "1_1") (pintype "passive"))
      (node (ref "C6") (pin "1") (pinfunction "1_1") (pintype "passive"))
      (node (ref "C7") (pin "1") (pinfunction "1_1") (pintype "passive"))
      (node (ref "C8") (pin "1") (pinfunction "1_1") (pintype "passive"))
      (node (ref "C9") (pin "1") (pinfunction "1_1") (pintype "passive"))
      (node (ref "CONN1") (pin "17") (pinfunction "17_17") (pintype "passive"))
      (node (ref "CONN1") (pin "18") (pinfunction "18_18") (pintype "passive"))
      (node (ref "CONN1") (pin "19") (pinfunction "19_19") (pintype "passive"))
      (node (ref "CONN1") (pin "20") (pinfunction "20_20") (pintype "passive"))
      (node (ref "CONN1") (pin "21") (pinfunction "21_21") (pintype "passive"))
      (node (ref "CONN1") (pin "23") (pinfunction "23_23") (pintype "passive"))
      (node (ref "CONN1") (pin "25") (pinfunction "25_25") (pintype "passive"))
      (node (ref "CONN1") (pin "27") (pinfunction "27_27") (pintype "passive"))
      (node (ref "CONN1") (pin "29") (pinfunction "29_29") (pintype "passive"))
      (node (ref "CONN1") (pin "31") (pinfunction "31_31") (pintype "passive"))
      (node (ref "CONN2") (pin "17") (pinfunction "17_17") (pintype "passive"))
      (node (ref "CONN2") (pin "18") (pinfunction "18_18") (pintype "passive"))
      (node (ref "CONN2") (pin "19") (pinfunction "19_19") (pintype "passive"))
      (node (ref "CONN2") (pin "20") (pinfunction "20_20") (pintype "passive"))
      (node (ref "CONN2") (pin "21") (pinfunction "21_21") (pintype "passive"))
      (node (ref "CONN2") (pin "23") (pinfunction "23_23") (pintype "passive"))
      (node (ref "CONN2") (pin "25") (pinfunction "25_25") (pintype "passive"))
      (node (ref "CONN2") (pin "27") (pinfunction "27_27") (pintype "passive"))
      (node (ref "CONN2") (pin "29") (pinfunction "29_29") (pintype "passive"))
      (node (ref "CONN2") (pin "31") (pinfunction "31_31") (pintype "passive"))
      (node (ref "CONN3") (pin "10") (pinfunction "10_10") (pintype "passive"))
      (node (ref "CONN3") (pin "5") (pinfunction "5_5") (pintype "passive"))
      (node (ref "CONN3") (pin "6") (pinfunction "6_6") (pintype "passive"))
      (node (ref "CONN3") (pin "7") (pinfunction "7_7") (pintype "passive"))
      (node (ref "CONN3") (pin "8") (pinfunction "8_8") (pintype "passive"))
      (node (ref "CONN3") (pin "9") (pinfunction "9_9") (pintype "passive"))
      (node (ref "U1") (pin "10") (pinfunction "-UB_10") (pintype "power_in"))
      (node (ref "U10") (pin "14") (pinfunction "VSS_14") (pintype "power_in"))
      (node (ref "U11") (pin "14") (pinfunction "VSS_14") (pintype "power_in"))
      (node (ref "U12") (pin "14") (pinfunction "VSS_14") (pintype "power_in"))
      (node (ref "U2") (pin "10") (pinfunction "-UB_10") (pintype "power_in"))
      (node (ref "U5") (pin "16") (pinfunction "VSS_16") (pintype "power_in"))
      (node (ref "U5") (pin "24") (pinfunction "OE_24") (pintype "input"))
      (node (ref "U6") (pin "16") (pinfunction "VSS_16") (pintype "power_in"))
      (node (ref "U6") (pin "24") (pinfunction "OE_24") (pintype "input"))
      (node (ref "U7") (pin "10") (pinfunction "-UB_10") (pintype "power_in"))
      (node (ref "U8") (pin "10") (pinfunction "-UB_10") (pintype "power_in"))
      (node (ref "U9") (pin "14") (pinfunction "VSS_14") (pintype "power_in"))
    )
    (net (code "83") (name "Net-(U4E-I)") (class "Default")
      (node (ref "C13") (pin "1") (pinfunction "1_1") (pintype "passive"))
      (node (ref "R1") (pin "1") (pinfunction "1_1") (pintype "passive"))
      (node (ref "U4") (pin "11") (pinfunction "I_11") (pintype "input"))
    )
    (net (code "84") (name "VCC") (class "Default")
      (node (ref "C1") (pin "2") (pinfunction "2_2") (pintype "passive"))
      (node (ref "C10") (pin "2") (pinfunction "2_2") (pintype "passive"))
      (node (ref "C11") (pin "2") (pinfunction "2_2") (pintype "passive"))
      (node (ref "C12") (pin "2") (pinfunction "2_2") (pintype "passive"))
      (node (ref "C2") (pin "2") (pinfunction "2_2") (pintype "passive"))
      (node (ref "C3") (pin "2") (pinfunction "2_2") (pintype "passive"))
      (node (ref "C4") (pin "2") (pinfunction "2_2") (pintype "passive"))
      (node (ref "C5") (pin "2") (pinfunction "2_2") (pintype "passive"))
      (node (ref "C6") (pin "2") (pinfunction "2_2") (pintype "passive"))
      (node (ref "C7") (pin "2") (pinfunction "2_2") (pintype "passive"))
      (node (ref "C8") (pin "2") (pinfunction "2_2") (pintype "passive"))
      (node (ref "C9") (pin "2") (pinfunction "2_2") (pintype "passive"))
      (node (ref "CONN1") (pin "38") (pinfunction "38_38") (pintype "passive"))
      (node (ref "CONN1") (pin "40") (pinfunction "40_40") (pintype "passive"))
      (node (ref "CONN3") (pin "1") (pinfunction "1_1") (pintype "passive"))
      (node (ref "CONN3") (pin "2") (pinfunction "2_2") (pintype "passive"))
      (node (ref "CONN3") (pin "3") (pinfunction "3_3") (pintype "passive"))
      (node (ref "CONN3") (pin "4") (pinfunction "4_4") (pintype "passive"))
      (node (ref "U1") (pin "20") (pinfunction "+UB_20") (pintype "power_in"))
      (node (ref "U10") (pin "26") (pinfunction "CS2_26") (pintype "input"))
      (node (ref "U10") (pin "28") (pinfunction "VCC_28") (pintype "power_in"))
      (node (ref "U11") (pin "26") (pinfunction "CS2_26") (pintype "input"))
      (node (ref "U11") (pin "28") (pinfunction "VCC_28") (pintype "power_in"))
      (node (ref "U12") (pin "26") (pinfunction "CS2_26") (pintype "input"))
      (node (ref "U12") (pin "28") (pinfunction "VCC_28") (pintype "power_in"))
      (node (ref "U2") (pin "20") (pinfunction "+UB_20") (pintype "power_in"))
      (node (ref "U5") (pin "32") (pinfunction "VCC_32") (pintype "power_in"))
      (node (ref "U6") (pin "32") (pinfunction "VCC_32") (pintype "power_in"))
      (node (ref "U7") (pin "20") (pinfunction "+UB_20") (pintype "power_in"))
      (node (ref "U8") (pin "20") (pinfunction "+UB_20") (pintype "power_in"))
      (node (ref "U9") (pin "26") (pinfunction "CS2_26") (pintype "input"))
      (node (ref "U9") (pin "28") (pinfunction "VCC_28") (pintype "power_in"))
    )
    (net (code "85") (name "unconnected-(CONN1-Pad33)") (class "Default")
      (node (ref "CONN1") (pin "33") (pinfunction "33_33") (pintype "passive"))
    )
    (net (code "86") (name "unconnected-(CONN2-Pad26)") (class "Default")
      (node (ref "CONN2") (pin "26") (pinfunction "26_26") (pintype "passive"))
    )
    (net (code "87") (name "unconnected-(CONN2-Pad33)") (class "Default")
      (node (ref "CONN2") (pin "33") (pinfunction "33_33") (pintype "passive"))
    )
    (net (code "88") (name "unconnected-(CONN3-Pad11)") (class "Default")
      (node (ref "CONN3") (pin "11") (pinfunction "11_11") (pintype "passive"))
    )
    (net (code "89") (name "unconnected-(CONN3-Pad12)") (class "Default")
      (node (ref "CONN3") (pin "12") (pinfunction "12_12") (pintype "passive"))
    )
    (net (code "90") (name "unconnected-(CONN3-Pad13)") (class "Default")
      (node (ref "CONN3") (pin "13") (pinfunction "13_13") (pintype "passive"))
    )
    (net (code "91") (name "unconnected-(CONN3-Pad14)") (class "Default")
      (node (ref "CONN3") (pin "14") (pinfunction "14_14") (pintype "passive"))
    )
    (net (code "92") (name "unconnected-(CONN3-Pad15)") (class "Default")
      (node (ref "CONN3") (pin "15") (pinfunction "15_15") (pintype "passive"))
    )
    (net (code "93") (name "unconnected-(CONN3-Pad16)") (class "Default")
      (node (ref "CONN3") (pin "16") (pinfunction "16_16") (pintype "passive"))
    )
    (net (code "94") (name "unconnected-(CONN3-Pad17)") (class "Default")
      (node (ref "CONN3") (pin "17") (pinfunction "17_17") (pintype "passive"))
    )
    (net (code "95") (name "unconnected-(CONN3-Pad18)") (class "Default")
      (node (ref "CONN3") (pin "18") (pinfunction "18_18") (pintype "passive"))
    )
    (net (code "96") (name "unconnected-(CONN3-Pad19)") (class "Default")
      (node (ref "CONN3") (pin "19") (pinfunction "19_19") (pintype "passive"))
    )
    (net (code "97") (name "unconnected-(CONN3-Pad20)") (class "Default")
      (node (ref "CONN3") (pin "20") (pinfunction "20_20") (pintype "passive"))
    )
    (net (code "98") (name "unconnected-(CONN3-Pad21)") (class "Default")
      (node (ref "CONN3") (pin "21") (pinfunction "21_21") (pintype "passive"))
    )
    (net (code "99") (name "unconnected-(CONN3-Pad22)") (class "Default")
      (node (ref "CONN3") (pin "22") (pinfunction "22_22") (pintype "passive"))
    )
    (net (code "100") (name "unconnected-(CONN3-Pad23)") (class "Default")
      (node (ref "CONN3") (pin "23") (pinfunction "23_23") (pintype "passive"))
    )
    (net (code "101") (name "unconnected-(CONN3-Pad24)") (class "Default")
      (node (ref "CONN3") (pin "24") (pinfunction "24_24") (pintype "passive"))
    )
    (net (code "102") (name "unconnected-(CONN3-Pad25)") (class "Default")
      (node (ref "CONN3") (pin "25") (pinfunction "25_25") (pintype "passive"))
    )
    (net (code "103") (name "unconnected-(CONN3-Pad28)") (class "Default")
      (node (ref "CONN3") (pin "28") (pinfunction "28_28") (pintype "passive"))
    )
    (net (code "104") (name "unconnected-(CONN3-Pad30)") (class "Default")
      (node (ref "CONN3") (pin "30") (pinfunction "30_30") (pintype "passive"))
    )
    (net (code "105") (name "unconnected-(CONN3-Pad53)") (class "Default")
      (node (ref "CONN3") (pin "53") (pinfunction "53_53") (pintype "passive"))
    )
    (net (code "106") (name "unconnected-(CONN3-Pad55)") (class "Default")
      (node (ref "CONN3") (pin "55") (pinfunction "55_55") (pintype "passive"))
    )
    (net (code "107") (name "unconnected-(CONN3-Pad56)") (class "Default")
      (node (ref "CONN3") (pin "56") (pinfunction "56_56") (pintype "passive"))
    )
    (net (code "108") (name "unconnected-(CONN3-Pad57)") (class "Default")
      (node (ref "CONN3") (pin "57") (pinfunction "57_57") (pintype "passive"))
    )
    (net (code "109") (name "unconnected-(CONN3-Pad58)") (class "Default")
      (node (ref "CONN3") (pin "58") (pinfunction "58_58") (pintype "passive"))
    )
    (net (code "110") (name "unconnected-(CONN3-Pad59)") (class "Default")
      (node (ref "CONN3") (pin "59") (pinfunction "59_59") (pintype "passive"))
    )
    (net (code "111") (name "unconnected-(CONN3-Pad60)") (class "Default")
      (node (ref "CONN3") (pin "60") (pinfunction "60_60") (pintype "passive"))
    )
    (net (code "112") (name "unconnected-(U3A-O2-Pad16)") (class "Default")
      (node (ref "U3") (pin "16") (pinfunction "O2_16") (pintype "bidirectional"))
    )
    (net (code "113") (name "unconnected-(U3A-O3-Pad17)") (class "Default")
      (node (ref "U3") (pin "17") (pinfunction "O3_17") (pintype "bidirectional"))
    )
    (net (code "114") (name "unconnected-(U3A-O4-Pad18)") (class "Default")
      (node (ref "U3") (pin "18") (pinfunction "O4_18") (pintype "bidirectional"))
    )
    (net (code "115") (name "unconnected-(U3A-O5-Pad19)") (class "Default")
      (node (ref "U3") (pin "19") (pinfunction "O5_19") (pintype "bidirectional"))
    )
    (net (code "116") (name "unconnected-(U9-NC-Pad1)") (class "Default")
      (node (ref "U9") (pin "1") (pinfunction "NC_1") (pintype "no_connect"))
    )
    (net (code "117") (name "unconnected-(U10-NC-Pad1)") (class "Default")
      (node (ref "U10") (pin "1") (pinfunction "NC_1") (pintype "no_connect"))
    )
    (net (code "118") (name "unconnected-(U11-NC-Pad1)") (class "Default")
      (node (ref "U11") (pin "1") (pinfunction "NC_1") (pintype "no_connect"))
    )
    (net (code "119") (name "unconnected-(U12-NC-Pad1)") (class "Default")
      (node (ref "U12") (pin "1") (pinfunction "NC_1") (pintype "no_connect"))
    )
  )
)
